# lhsspi.net
KiCad netlist of a schematic drawn in EAGLE
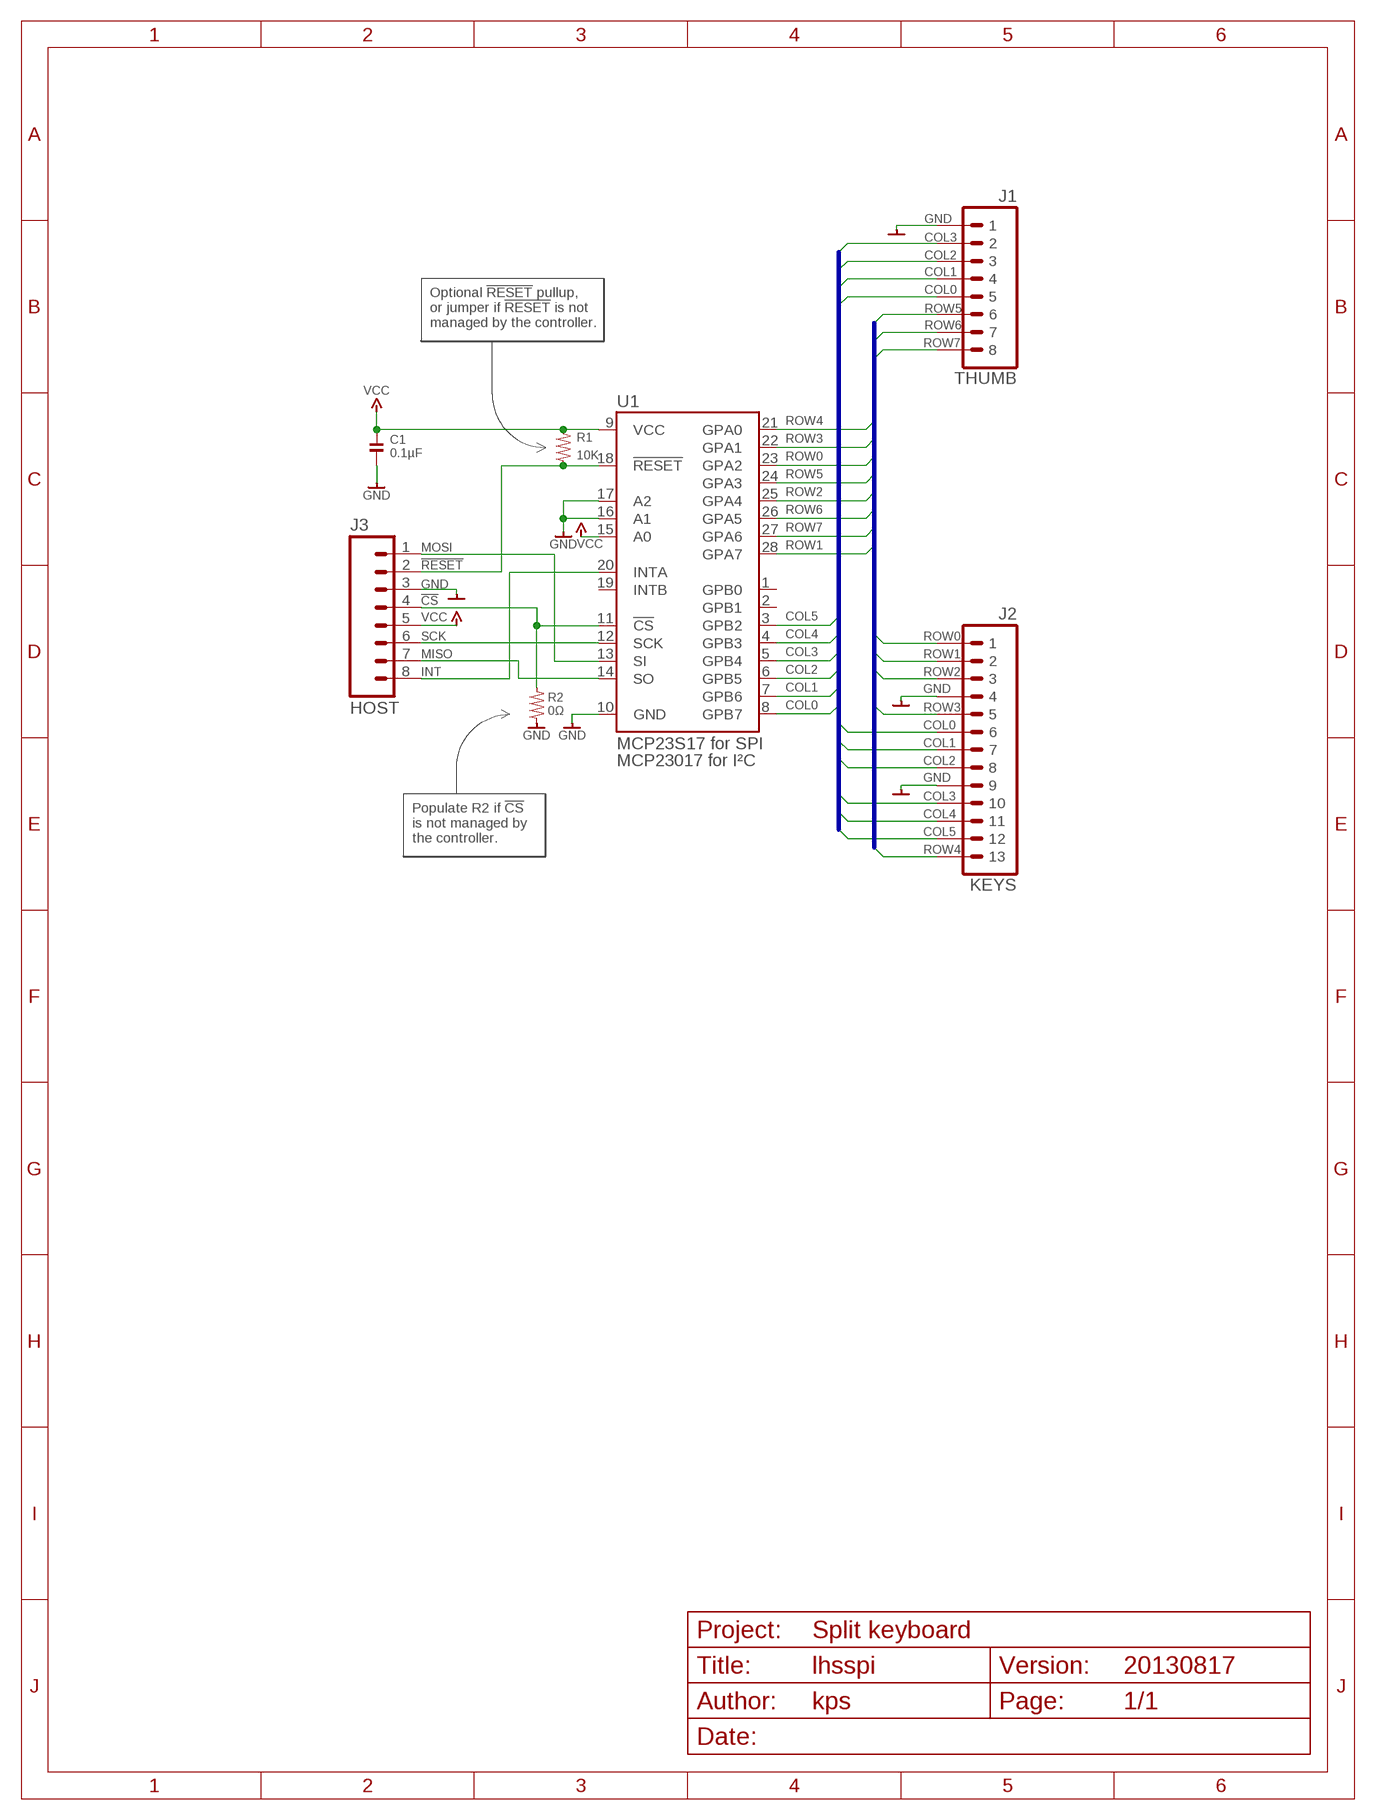
[diagram p0: schematic, sheet 1]

(export (version "E")
  (design (tool "Eeschema 10.0.6"))
  (components
    (comp (ref "C1")
      (value "0.1µF")
      (footprint "eagle-import:SMD-1206")
      (libsource (lib "eagle-import") (part "CAPACITOR-SCH200-1206"))
    )
    (comp (ref "J1")
      (value "THUMB")
      (footprint "eagle-import:J-8-2510")
      (libsource (lib "eagle-import") (part "J-8-2510"))
    )
    (comp (ref "J2")
      (value "KEYS")
      (footprint "eagle-import:J-13-100-ALT-L")
      (libsource (lib "eagle-import") (part "J-13-100-ALT-L"))
    )
    (comp (ref "J3")
      (value "HOST")
      (footprint "eagle-import:J-8-2510")
      (libsource (lib "eagle-import") (part "wtf_J-8-2510"))
    )
    (comp (ref "R1")
      (value "10K")
      (footprint "eagle-import:SMD-1206")
      (libsource (lib "eagle-import") (part "RESISTOR-1206"))
    )
    (comp (ref "R2")
      (value "0Ω")
      (footprint "eagle-import:SMD-1206")
      (libsource (lib "eagle-import") (part "RESISTOR-1206"))
    )
    (comp (ref "U1")
      (value "MCP23S17 for SPI")
      (footprint "eagle-import:IC-28-SOIC-300")
      (libsource (lib "eagle-import") (part "IC-MCP23S17-SOIC"))
    )
  )
  (nets
    (net (code "1") (name "/COL0") (class "Default")
      (node (ref "J1") (pin "5") (pinfunction "5_5") (pintype "passive"))
      (node (ref "J2") (pin "P6") (pinfunction "6_P6") (pintype "passive"))
      (node (ref "U1") (pin "8") (pinfunction "GPB7_8") (pintype "bidirectional"))
    )
    (net (code "2") (name "/COL1") (class "Default")
      (node (ref "J1") (pin "4") (pinfunction "4_4") (pintype "passive"))
      (node (ref "J2") (pin "P7") (pinfunction "7_P7") (pintype "passive"))
      (node (ref "U1") (pin "7") (pinfunction "GPB6_7") (pintype "bidirectional"))
    )
    (net (code "3") (name "/COL2") (class "Default")
      (node (ref "J1") (pin "3") (pinfunction "3_3") (pintype "passive"))
      (node (ref "J2") (pin "P8") (pinfunction "8_P8") (pintype "passive"))
      (node (ref "U1") (pin "6") (pinfunction "GPB5_6") (pintype "bidirectional"))
    )
    (net (code "4") (name "/COL3") (class "Default")
      (node (ref "J1") (pin "2") (pinfunction "2_2") (pintype "passive"))
      (node (ref "J2") (pin "P10") (pinfunction "10_P10") (pintype "passive"))
      (node (ref "U1") (pin "5") (pinfunction "GPB4_5") (pintype "bidirectional"))
    )
    (net (code "5") (name "/COL4") (class "Default")
      (node (ref "J2") (pin "P11") (pinfunction "11_P11") (pintype "passive"))
      (node (ref "U1") (pin "4") (pinfunction "GPB3_4") (pintype "bidirectional"))
    )
    (net (code "6") (name "/COL5") (class "Default")
      (node (ref "J2") (pin "P12") (pinfunction "12_P12") (pintype "passive"))
      (node (ref "U1") (pin "3") (pinfunction "GPB2_3") (pintype "bidirectional"))
    )
    (net (code "7") (name "/INT") (class "Default")
      (node (ref "J3") (pin "8") (pinfunction "8_8") (pintype "passive"))
      (node (ref "U1") (pin "20") (pinfunction "INTA_20") (pintype "output"))
    )
    (net (code "8") (name "/MISO") (class "Default")
      (node (ref "J3") (pin "7") (pinfunction "7_7") (pintype "passive"))
      (node (ref "U1") (pin "14") (pinfunction "SO_14") (pintype "output"))
    )
    (net (code "9") (name "/MOSI") (class "Default")
      (node (ref "J3") (pin "1") (pinfunction "1_1") (pintype "passive"))
      (node (ref "U1") (pin "13") (pinfunction "SI_13") (pintype "input"))
    )
    (net (code "10") (name "/ROW0") (class "Default")
      (node (ref "J2") (pin "P1") (pinfunction "1_P1") (pintype "passive"))
      (node (ref "U1") (pin "23") (pinfunction "GPA2_23") (pintype "bidirectional"))
    )
    (net (code "11") (name "/ROW1") (class "Default")
      (node (ref "J2") (pin "P2") (pinfunction "2_P2") (pintype "passive"))
      (node (ref "U1") (pin "28") (pinfunction "GPA7_28") (pintype "bidirectional"))
    )
    (net (code "12") (name "/ROW2") (class "Default")
      (node (ref "J2") (pin "P3") (pinfunction "3_P3") (pintype "passive"))
      (node (ref "U1") (pin "25") (pinfunction "GPA4_25") (pintype "bidirectional"))
    )
    (net (code "13") (name "/ROW3") (class "Default")
      (node (ref "J2") (pin "P5") (pinfunction "5_P5") (pintype "passive"))
      (node (ref "U1") (pin "22") (pinfunction "GPA1_22") (pintype "bidirectional"))
    )
    (net (code "14") (name "/ROW4") (class "Default")
      (node (ref "J2") (pin "P13") (pinfunction "13_P13") (pintype "passive"))
      (node (ref "U1") (pin "21") (pinfunction "GPA0_21") (pintype "bidirectional"))
    )
    (net (code "15") (name "/ROW5") (class "Default")
      (node (ref "J1") (pin "6") (pinfunction "6_6") (pintype "passive"))
      (node (ref "U1") (pin "24") (pinfunction "GPA3_24") (pintype "bidirectional"))
    )
    (net (code "16") (name "/ROW6") (class "Default")
      (node (ref "J1") (pin "7") (pinfunction "7_7") (pintype "passive"))
      (node (ref "U1") (pin "26") (pinfunction "GPA5_26") (pintype "bidirectional"))
    )
    (net (code "17") (name "/ROW7") (class "Default")
      (node (ref "J1") (pin "8") (pinfunction "8_8") (pintype "passive"))
      (node (ref "U1") (pin "27") (pinfunction "GPA6_27") (pintype "bidirectional"))
    )
    (net (code "18") (name "/SCK") (class "Default")
      (node (ref "J3") (pin "6") (pinfunction "6_6") (pintype "passive"))
      (node (ref "U1") (pin "12") (pinfunction "SCK_12") (pintype "input"))
    )
    (net (code "19") (name "/~{CS}") (class "Default")
      (node (ref "J3") (pin "4") (pinfunction "4_4") (pintype "passive"))
      (node (ref "R2") (pin "2") (pinfunction "2_2") (pintype "passive"))
      (node (ref "U1") (pin "11") (pinfunction "~{CS}_11") (pintype "input"))
    )
    (net (code "20") (name "/~{RESET}") (class "Default")
      (node (ref "J3") (pin "2") (pinfunction "2_2") (pintype "passive"))
      (node (ref "R1") (pin "1") (pinfunction "1_1") (pintype "passive"))
      (node (ref "U1") (pin "18") (pinfunction "~{RESET}_18") (pintype "input"))
    )
    (net (code "21") (name "GND") (class "Default")
      (node (ref "C1") (pin "2") (pinfunction "2_2") (pintype "passive"))
      (node (ref "J1") (pin "1") (pinfunction "1_1") (pintype "passive"))
      (node (ref "J2") (pin "P4") (pinfunction "4_P4") (pintype "passive"))
      (node (ref "J2") (pin "P9") (pinfunction "9_P9") (pintype "passive"))
      (node (ref "J3") (pin "3") (pinfunction "3_3") (pintype "passive"))
      (node (ref "R2") (pin "1") (pinfunction "1_1") (pintype "passive"))
      (node (ref "U1") (pin "10") (pinfunction "GND_10") (pintype "power_in"))
      (node (ref "U1") (pin "16") (pinfunction "A1_16") (pintype "input"))
      (node (ref "U1") (pin "17") (pinfunction "A2_17") (pintype "input"))
    )
    (net (code "22") (name "VCC") (class "Default")
      (node (ref "C1") (pin "1") (pinfunction "1_1") (pintype "passive"))
      (node (ref "J3") (pin "5") (pinfunction "5_5") (pintype "passive"))
      (node (ref "R1") (pin "2") (pinfunction "2_2") (pintype "passive"))
      (node (ref "U1") (pin "15") (pinfunction "A0_15") (pintype "input"))
      (node (ref "U1") (pin "9") (pinfunction "VCC_9") (pintype "power_in"))
    )
    (net (code "23") (name "unconnected-(U1-GPB0-Pad1)") (class "Default")
      (node (ref "U1") (pin "1") (pinfunction "GPB0_1") (pintype "bidirectional"))
    )
    (net (code "24") (name "unconnected-(U1-GPB1-Pad2)") (class "Default")
      (node (ref "U1") (pin "2") (pinfunction "GPB1_2") (pintype "bidirectional"))
    )
    (net (code "25") (name "unconnected-(U1-INTB-Pad19)") (class "Default")
      (node (ref "U1") (pin "19") (pinfunction "INTB_19") (pintype "output"))
    )
  )
)
